# 09_Parallel_Camera.net
KiCad netlist of a schematic drawn in Altium Designer
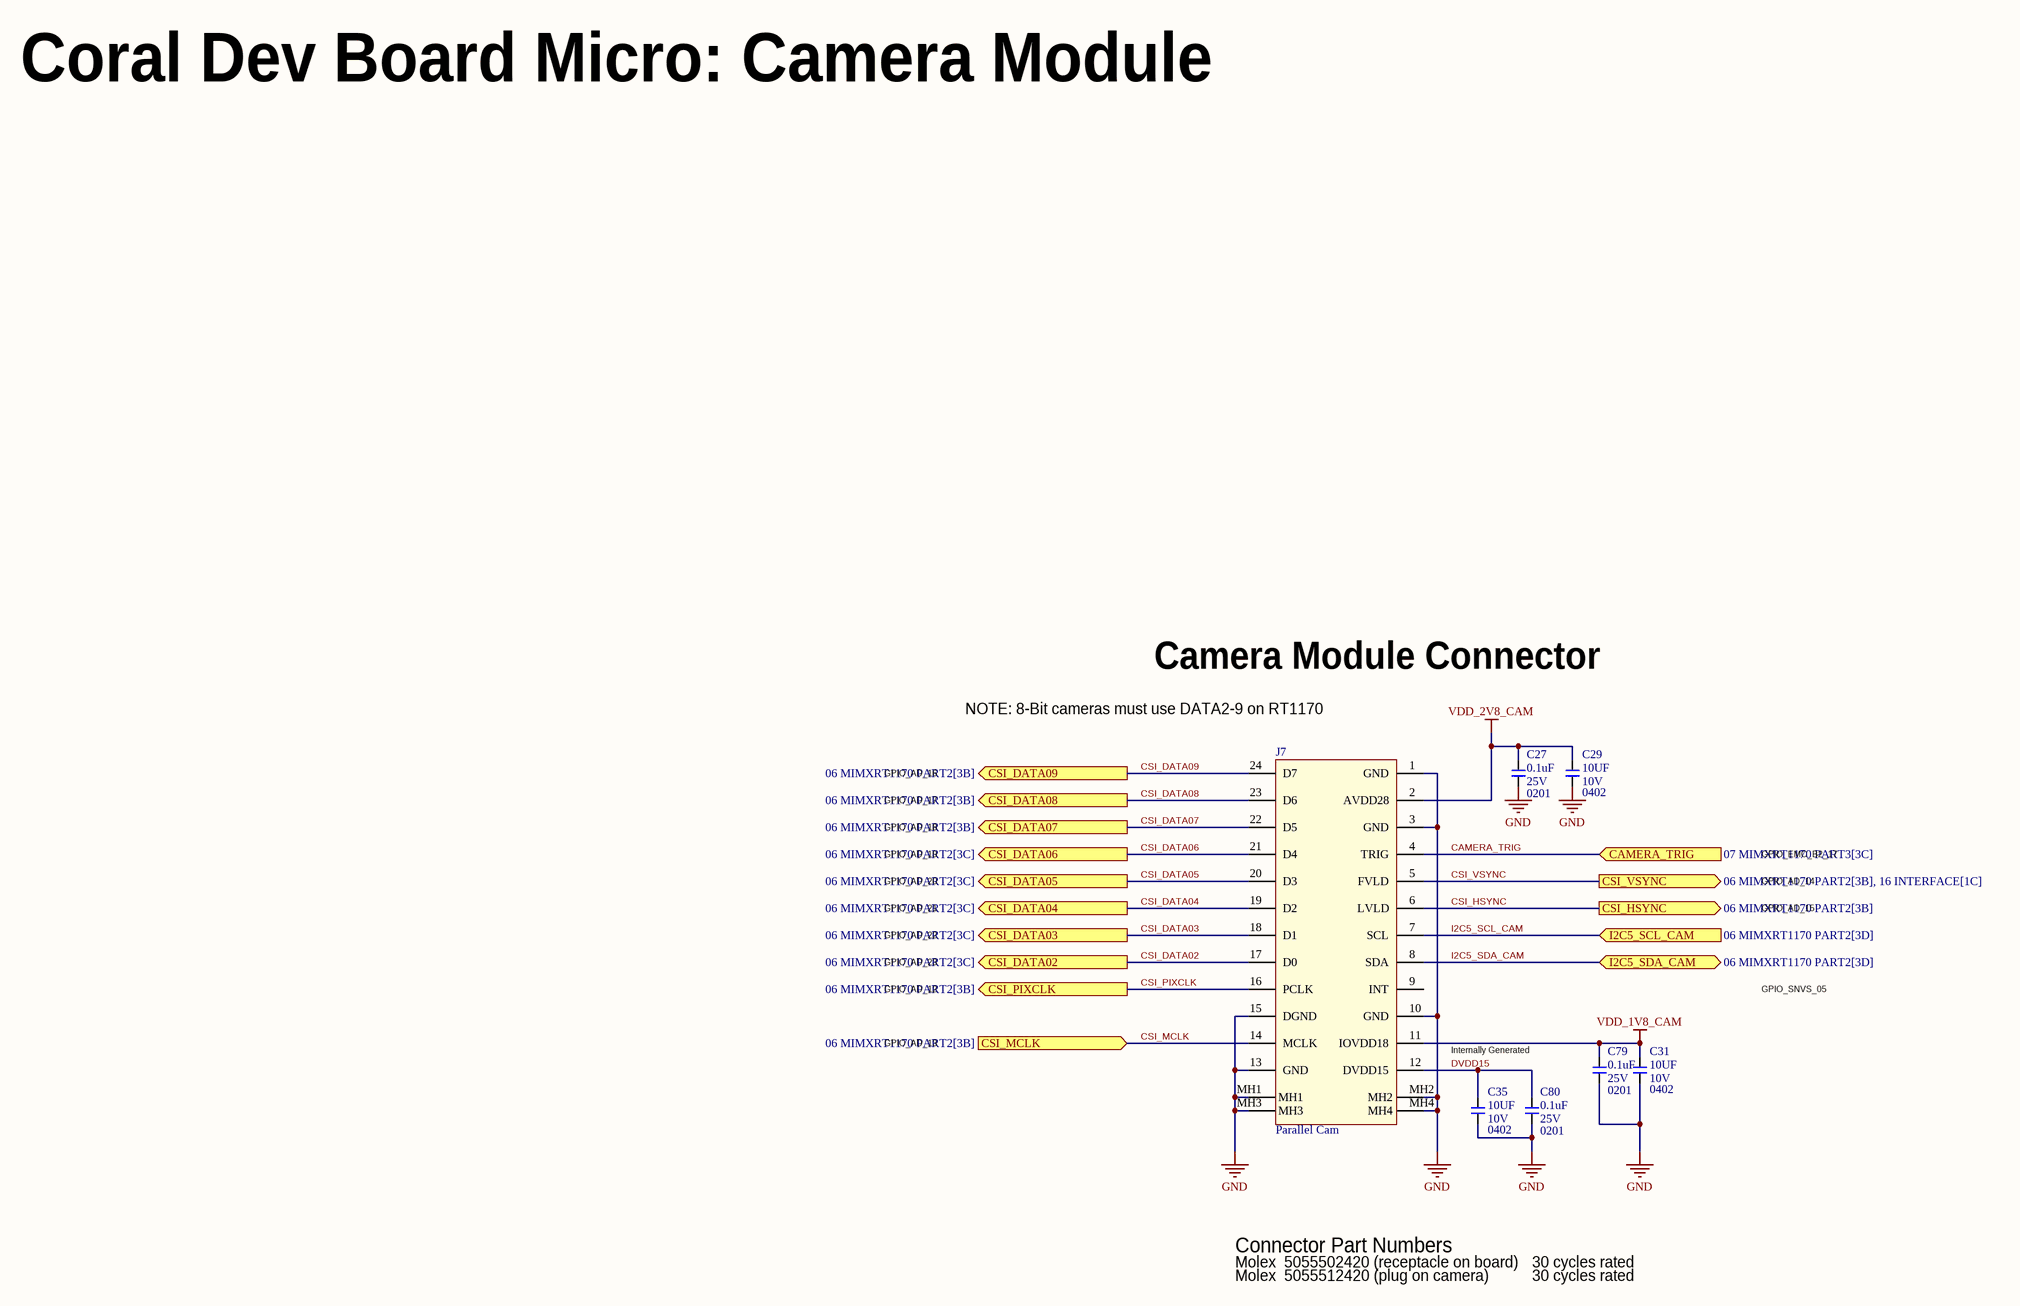
[diagram p0: 09 Parallel Camera.SchDoc]

(export (version "E")
  (design (tool "Eeschema 10.0.6"))
  (components
    (comp (ref "C27")
      (value "0.1uF")
      (footprint "C0201Y")
      (description "CAP, CER, X5R, 0.1uF, 25V, 20%, 0201, 0.33mm T")
      (fields
        (field (name "MFG") "MURATA")
        (field (name "PACKAGE") "0201")
        (field (name "VOLTAGE") "25V")
        (field (name "TOLERANCE") "20%")
      )
      (libsource (lib "AltiumReleaseLibDB") (part "__Template_Cap"))
    )
    (comp (ref "C29")
      (value "10UF")
      (footprint "C0402")
      (description "CAP, CER, X5R, 10uF, 10V, 20%, 0402, 0.7mm T")
      (fields
        (field (name "MFG") "SAMSUNG")
        (field (name "PACKAGE") "0402")
        (field (name "VOLTAGE") "10V")
        (field (name "TOLERANCE") "20%")
      )
      (libsource (lib "AltiumReleaseLibDB") (part "__Template_Cap"))
    )
    (comp (ref "C31")
      (value "10UF")
      (footprint "C0402")
      (description "CAP, CER, X5R, 10uF, 10V, 20%, 0402, 0.7mm T")
      (fields
        (field (name "MFG") "SAMSUNG")
        (field (name "PACKAGE") "0402")
        (field (name "VOLTAGE") "10V")
        (field (name "TOLERANCE") "20%")
      )
      (libsource (lib "AltiumReleaseLibDB") (part "__Template_Cap"))
    )
    (comp (ref "C35")
      (value "10UF")
      (footprint "C0402")
      (description "CAP, CER, X5R, 10uF, 10V, 20%, 0402, 0.7mm T")
      (fields
        (field (name "MFG") "SAMSUNG")
        (field (name "PACKAGE") "0402")
        (field (name "VOLTAGE") "10V")
        (field (name "TOLERANCE") "20%")
      )
      (libsource (lib "AltiumReleaseLibDB") (part "__Template_Cap"))
    )
    (comp (ref "C79")
      (value "0.1uF")
      (footprint "C0201Y")
      (description "CAP, CER, X5R, 0.1uF, 25V, 20%, 0201, 0.33mm T")
      (fields
        (field (name "MFG") "MURATA")
        (field (name "PACKAGE") "0201")
        (field (name "VOLTAGE") "25V")
        (field (name "TOLERANCE") "20%")
      )
      (libsource (lib "AltiumReleaseLibDB") (part "__Template_Cap"))
    )
    (comp (ref "C80")
      (value "0.1uF")
      (footprint "C0201Y")
      (description "CAP, CER, X5R, 0.1uF, 25V, 20%, 0201, 0.33mm T")
      (fields
        (field (name "MFG") "MURATA")
        (field (name "PACKAGE") "0201")
        (field (name "VOLTAGE") "25V")
        (field (name "TOLERANCE") "20%")
      )
      (libsource (lib "AltiumReleaseLibDB") (part "__Template_Cap"))
    )
    (comp (ref "J7")
      (value "1087")
      (footprint "Molex_5037722410_HM01B0")
      (description "HM01B0, CONN, RCPT, OUTER SHROUD, 2x12 PIN, 0.4MM P, 0.65MM H, GOLD, SM")
      (fields (field (name "MFG") "Molex") (field (name "MFG P/N") "Parallel Cam"))
      (libsource (lib "Valiant_P1") (part "1087"))
    )
  )
  (nets
    (net (code "1") (name "/CAMERA_TRIG") (class "Default")
      (node (ref "J7") (pin "4") (pinfunction "TRIG_4") (pintype "passive"))
    )
    (net (code "2") (name "/CSI_DATA02") (class "Default")
      (node (ref "J7") (pin "17") (pinfunction "D0_17") (pintype "passive"))
    )
    (net (code "3") (name "/CSI_DATA03") (class "Default")
      (node (ref "J7") (pin "18") (pinfunction "D1_18") (pintype "passive"))
    )
    (net (code "4") (name "/CSI_DATA04") (class "Default")
      (node (ref "J7") (pin "19") (pinfunction "D2_19") (pintype "passive"))
    )
    (net (code "5") (name "/CSI_DATA05") (class "Default")
      (node (ref "J7") (pin "20") (pinfunction "D3_20") (pintype "passive"))
    )
    (net (code "6") (name "/CSI_DATA06") (class "Default")
      (node (ref "J7") (pin "21") (pinfunction "D4_21") (pintype "passive"))
    )
    (net (code "7") (name "/CSI_DATA07") (class "Default")
      (node (ref "J7") (pin "22") (pinfunction "D5_22") (pintype "passive"))
    )
    (net (code "8") (name "/CSI_DATA08") (class "Default")
      (node (ref "J7") (pin "23") (pinfunction "D6_23") (pintype "passive"))
    )
    (net (code "9") (name "/CSI_DATA09") (class "Default")
      (node (ref "J7") (pin "24") (pinfunction "D7_24") (pintype "passive"))
    )
    (net (code "10") (name "/CSI_HSYNC") (class "Default")
      (node (ref "J7") (pin "6") (pinfunction "LVLD_6") (pintype "passive"))
    )
    (net (code "11") (name "/CSI_MCLK") (class "Default")
      (node (ref "J7") (pin "14") (pinfunction "MCLK_14") (pintype "passive"))
    )
    (net (code "12") (name "/CSI_PIXCLK") (class "Default")
      (node (ref "J7") (pin "16") (pinfunction "PCLK_16") (pintype "passive"))
    )
    (net (code "13") (name "/CSI_VSYNC") (class "Default")
      (node (ref "J7") (pin "5") (pinfunction "FVLD_5") (pintype "passive"))
    )
    (net (code "14") (name "/DVDD15") (class "Default")
      (node (ref "C35") (pin "1") (pintype "passive"))
      (node (ref "C80") (pin "1") (pintype "passive"))
      (node (ref "J7") (pin "12") (pinfunction "DVDD15_12") (pintype "passive"))
    )
    (net (code "15") (name "/I2C5_SCL_CAM") (class "Default")
      (node (ref "J7") (pin "7") (pinfunction "SCL_7") (pintype "passive"))
    )
    (net (code "16") (name "/I2C5_SDA_CAM") (class "Default")
      (node (ref "J7") (pin "8") (pinfunction "SDA_8") (pintype "passive"))
    )
    (net (code "17") (name "GND") (class "Default")
      (node (ref "C27") (pin "2") (pintype "passive"))
      (node (ref "C29") (pin "2") (pintype "passive"))
      (node (ref "C31") (pin "2") (pintype "passive"))
      (node (ref "C35") (pin "2") (pintype "passive"))
      (node (ref "C79") (pin "2") (pintype "passive"))
      (node (ref "C80") (pin "2") (pintype "passive"))
      (node (ref "J7") (pin "1") (pinfunction "GND_1") (pintype "passive"))
      (node (ref "J7") (pin "10") (pinfunction "GND_10") (pintype "passive"))
      (node (ref "J7") (pin "13") (pinfunction "GND_13") (pintype "passive"))
      (node (ref "J7") (pin "15") (pinfunction "DGND_15") (pintype "passive"))
      (node (ref "J7") (pin "3") (pinfunction "GND_3") (pintype "passive"))
      (node (ref "J7") (pin "MH1") (pinfunction "MH1_MH1") (pintype "passive"))
      (node (ref "J7") (pin "MH2") (pinfunction "MH2_MH2") (pintype "passive"))
      (node (ref "J7") (pin "MH3") (pinfunction "MH3_MH3") (pintype "passive"))
      (node (ref "J7") (pin "MH4") (pinfunction "MH4_MH4") (pintype "passive"))
    )
    (net (code "18") (name "VDD_1V8_CAM") (class "Default")
      (node (ref "C31") (pin "1") (pintype "passive"))
      (node (ref "C79") (pin "1") (pintype "passive"))
      (node (ref "J7") (pin "11") (pinfunction "IOVDD18_11") (pintype "passive"))
    )
    (net (code "19") (name "VDD_2V8_CAM") (class "Default")
      (node (ref "C27") (pin "1") (pintype "passive"))
      (node (ref "C29") (pin "1") (pintype "passive"))
      (node (ref "J7") (pin "2") (pinfunction "AVDD28_2") (pintype "passive"))
    )
    (net (code "20") (name "unconnected-(J7-INT-Pad9)") (class "Default")
      (node (ref "J7") (pin "9") (pinfunction "INT_9") (pintype "passive"))
    )
  )
)
